# Cell2_Balancing.net
KiCad netlist of a schematic drawn in Altium Designer
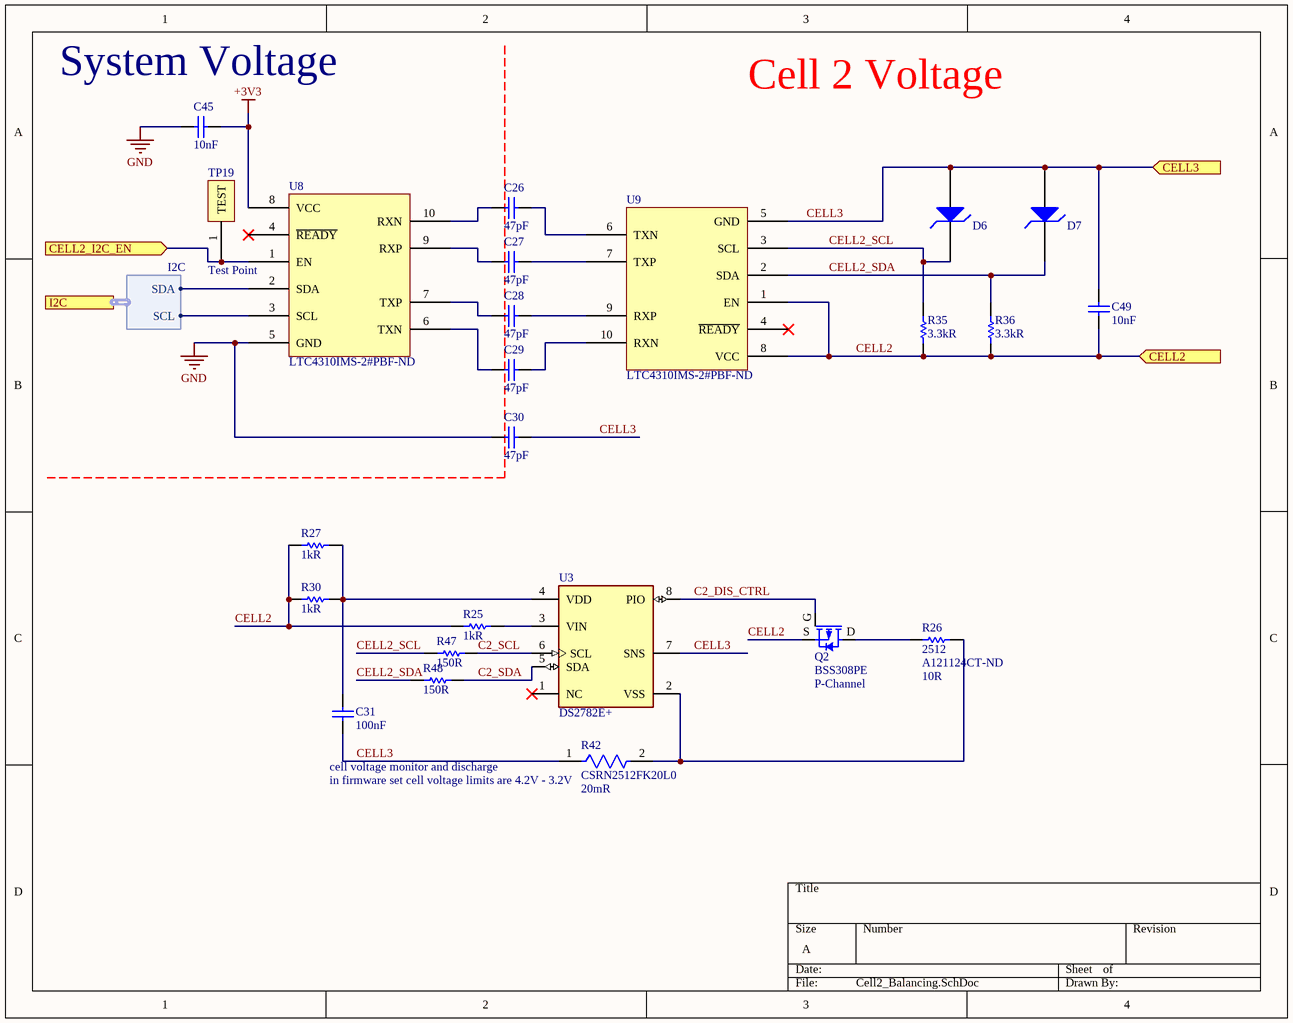
[diagram p0: Cell2_Balancing.SchDoc]

(export (version "E")
  (design (tool "Eeschema 10.0.6"))
  (components
    (comp (ref "C26")
      (value "06031A470FAT2A")
      (footprint "CAPC1608X90X35ML15T15")
      (fields (field (name "MANUFACTURER") "AVX Interconnect / Elco") (field (name "CAPACITANCE") "47pF"))
      (libsource (lib "Altium Content Vault") (part "CAP"))
    )
    (comp (ref "C27")
      (value "06031A470FAT2A")
      (footprint "CAPC1608X90X35ML15T15")
      (fields (field (name "MANUFACTURER") "AVX Interconnect / Elco") (field (name "CAPACITANCE") "47pF"))
      (libsource (lib "Altium Content Vault") (part "CAP"))
    )
    (comp (ref "C28")
      (value "06031A470FAT2A")
      (footprint "CAPC1608X90X35ML15T15")
      (fields (field (name "MANUFACTURER") "AVX Interconnect / Elco") (field (name "CAPACITANCE") "47pF"))
      (libsource (lib "Altium Content Vault") (part "CAP"))
    )
    (comp (ref "C29")
      (value "06031A470FAT2A")
      (footprint "CAPC1608X90X35ML15T15")
      (fields (field (name "MANUFACTURER") "AVX Interconnect / Elco") (field (name "CAPACITANCE") "47pF"))
      (libsource (lib "Altium Content Vault") (part "CAP"))
    )
    (comp (ref "C30")
      (value "06031A470FAT2A")
      (footprint "CAPC1608X90X35ML15T15")
      (fields (field (name "MANUFACTURER") "AVX Interconnect / Elco") (field (name "CAPACITANCE") "47pF"))
      (libsource (lib "Altium Content Vault") (part "CAP"))
    )
    (comp (ref "C31")
      (value "Capacitor 0402")
      (footprint "C0402")
      (description "CAP CER 0.1UF 25V X5R 0402 / High Value Multilayer Ceramic Capacitors (High dielectric type)")
      (fields
        (field (name "MANUFACTURER") "Taiyo Yuden")
        (field (name "MANUFACTURER PART NUMBER") "TMK105BJ104KV-F")
        (field (name "CAPACITANCE") "100nF")
      )
      (libsource (lib "Wally_BMS") (part "Capacitor 0402"))
    )
    (comp (ref "C45")
      (value "Capacitor 0402")
      (footprint "C0402")
      (description "Cap Ceramic 0.01uF 25V X7R 10% Pad SMD 0402 125C T/R")
      (fields
        (field (name "MANUFACTURER") "Samsung")
        (field (name "MANUFACTURER PART NUMBER") "CL05B103KA5NNNC")
        (field (name "CAPACITANCE") "10nF")
      )
      (libsource (lib "Wally_BMS") (part "Capacitor 0402"))
    )
    (comp (ref "C49")
      (value "Capacitor 0402")
      (footprint "C0402")
      (description "Cap Ceramic 0.01uF 25V X7R 10% Pad SMD 0402 125C T/R")
      (fields
        (field (name "MANUFACTURER") "Samsung")
        (field (name "MANUFACTURER PART NUMBER") "CL05B103KA5NNNC")
        (field (name "CAPACITANCE") "10nF")
      )
      (libsource (lib "Wally_BMS") (part "Capacitor 0402"))
    )
    (comp (ref "D6")
      (value "BZT52C4V7LP-7")
      (footprint "bzt52c4v7lp-7")
      (description "BZT52C4V7LP Series 4.7 V 10 mA Surface Mount Zener Diode - DFN1006-2")
      (fields (field (name "MANUFACTURER") "Diodes") (field (name "TOLERANCE") "6%"))
      (libsource (lib "Wally_BMS") (part "BZT52C4V7LP-7"))
    )
    (comp (ref "D7")
      (value "BZT52C4V7LP-7")
      (footprint "bzt52c4v7lp-7")
      (description "BZT52C4V7LP Series 4.7 V 10 mA Surface Mount Zener Diode - DFN1006-2")
      (fields (field (name "MANUFACTURER") "Diodes") (field (name "TOLERANCE") "6%"))
      (libsource (lib "Wally_BMS") (part "BZT52C4V7LP-7"))
    )
    (comp (ref "Q2")
      (value "BSS308PE")
      (footprint "BSS308PE")
      (description "MOSFET P-CH 30V 2A SOT23")
      (fields (field (name "FET TYPE") "P-Channel"))
      (libsource (lib "Transistors") (part "BSS308PE"))
    )
    (comp (ref "R25")
      (value "Resistor 0402")
      (footprint "RES0402")
      (description "Res Thick Film 0402 1K Ohm 1% 0.063W(1/16W) ±100ppm/C Pad SMD Automotive T/R")
      (fields
        (field (name "MANUFACTURER") "Stackpole Electronics")
        (field (name "MANUFACTURER PART NUMBER") "RMCF0402FT1K00")
        (field (name "RESISTANCE") "1kR")
      )
      (libsource (lib "Wally_BMS") (part "Resistor 0402"))
    )
    (comp (ref "R26")
      (value "Resistor 2512")
      (footprint "RES2512")
      (fields
        (field (name "PACKAGE / CASE") "2512")
        (field (name "SUPPLIER PART NUMBER 1") "A121124CT-ND")
        (field (name "MANUFACTURER") "TE Connectivity CGS")
        (field (name "MANUFACTURER PART NUMBER") "1-2176230-4")
        (field (name "RESISTANCE") "10R")
        (field (name "TOLERANCE") "5%")
      )
      (libsource (lib "Wally_BMS") (part "Resistor 2512"))
    )
    (comp (ref "R27")
      (value "Resistor 0402")
      (footprint "RES0402")
      (description "Res Thick Film 0402 1K Ohm 1% 0.063W(1/16W) ±100ppm/C Pad SMD Automotive T/R")
      (fields
        (field (name "MANUFACTURER") "Stackpole Electronics")
        (field (name "MANUFACTURER PART NUMBER") "RMCF0402FT1K00")
        (field (name "RESISTANCE") "1kR")
      )
      (libsource (lib "Wally_BMS") (part "Resistor 0402"))
    )
    (comp (ref "R30")
      (value "Resistor 0402")
      (footprint "RES0402")
      (description "Res Thick Film 0402 1K Ohm 1% 0.063W(1/16W) ±100ppm/C Pad SMD Automotive T/R")
      (fields
        (field (name "MANUFACTURER") "Stackpole Electronics")
        (field (name "MANUFACTURER PART NUMBER") "RMCF0402FT1K00")
        (field (name "RESISTANCE") "1kR")
      )
      (libsource (lib "Wally_BMS") (part "Resistor 0402"))
    )
    (comp (ref "R35")
      (value "Resistor 0402")
      (footprint "RES0402")
      (description "Res Thin Film 0402 3.3K Ohm 1% 1/16W ±50ppm/°C Molded SMD SMD Paper T/R")
      (fields
        (field (name "MANUFACTURER") "Yageo")
        (field (name "MANUFACTURER PART NUMBER") "RT0402FRE073K3L")
        (field (name "RESISTANCE") "3.3kR")
      )
      (libsource (lib "Wally_BMS") (part "Resistor 0402"))
    )
    (comp (ref "R36")
      (value "Resistor 0402")
      (footprint "RES0402")
      (description "Res Thin Film 0402 3.3K Ohm 1% 1/16W ±50ppm/°C Molded SMD SMD Paper T/R")
      (fields
        (field (name "MANUFACTURER") "Yageo")
        (field (name "MANUFACTURER PART NUMBER") "RT0402FRE073K3L")
        (field (name "RESISTANCE") "3.3kR")
      )
      (libsource (lib "Wally_BMS") (part "Resistor 0402"))
    )
    (comp (ref "R42")
      (value "CSRN2512FK20L0")
      (footprint "FP-CSRN2512-IPC_C")
      (description "Res Thick Film 2512 20mΩ 1% 2W ±200ppm/°C Molded SMD Plastic T/R")
      (fields (field (name "RESISTANCE") "20mR") (field (name "TOLERANCE") "1%"))
      (libsource (lib "Altium Content Vault") (part "1029c3af85768c4190bb7ad29bc67b5"))
    )
    (comp (ref "R47")
      (value "Resistor 0402")
      (footprint "RES0402")
      (description "Res Thin Film 0402 150 Ohm 1% 1/16W ±50ppm/°C Molded SMD SMD Paper T/R")
      (fields
        (field (name "MANUFACTURER") "Yageo")
        (field (name "MANUFACTURER PART NUMBER") "RT0402FRE07150RL")
        (field (name "RESISTANCE") "150R")
      )
      (libsource (lib "Wally_BMS") (part "Resistor 0402"))
    )
    (comp (ref "R48")
      (value "Resistor 0402")
      (footprint "RES0402")
      (description "Res Thin Film 0402 150 Ohm 1% 1/16W ±50ppm/°C Molded SMD SMD Paper T/R")
      (fields
        (field (name "MANUFACTURER") "Yageo")
        (field (name "MANUFACTURER PART NUMBER") "RT0402FRE07150RL")
        (field (name "RESISTANCE") "150R")
      )
      (libsource (lib "Wally_BMS") (part "Resistor 0402"))
    )
    (comp (ref "TP19")
      (value "Test Point")
      (footprint "TEST POINT")
      (libsource (lib "Wally_BMS") (part "Test Point"))
    )
    (comp (ref "U3")
      (value "DS2782E+")
      (footprint "FP-H8-2-MFG")
      (description "IC FUEL GAUGE BATT 8TSSOP")
      (fields
        (field (name "OCTOPART") "https://octopart.com/ds2782e%2B-maxim+integrated-8045252")
        (field (name "MANUFACTURER") "Maxim")
      )
      (libsource (lib "Altium Content Vault") (part "f9098ddd067e7739cd521d50be25c58"))
    )
    (comp (ref "U8")
      (value "LTC4310IMS-2#PBF-ND")
      (footprint "MSOP-10_MS_LIT")
      (description "DIGITAL ISOLATOR 2CH I2C 10MSOP")
      (libsource (lib "") (part "LTC4310IMS-2#PBF_1"))
    )
    (comp (ref "U9")
      (value "LTC4310IMS-2#PBF-ND")
      (footprint "MSOP-10_MS_LIT")
      (description "DIGITAL ISOLATOR 2CH I2C 10MSOP")
      (libsource (lib "Wally_BMS") (part "LTC4310IMS-2#PBF"))
    )
  )
  (nets
    (net (code "2") (name "+3V3") (class "Default")
      (node (ref "C45") (pin "1") (pinfunction "1_1") (pintype "passive"))
      (node (ref "U8") (pin "8") (pinfunction "VCC_8") (pintype "passive"))
    )
    (net (code "3") (name "/C2_DIS_CTRL") (class "Default")
      (node (ref "Q2") (pin "G") (pinfunction "G_G") (pintype "passive"))
      (node (ref "U3") (pin "8") (pinfunction "PIO_8") (pintype "bidirectional"))
    )
    (net (code "4") (name "/C2_SCL") (class "Default")
      (node (ref "R47") (pin "1") (pinfunction "1_1") (pintype "passive"))
      (node (ref "U3") (pin "6") (pinfunction "SCL_6") (pintype "input"))
    )
    (net (code "5") (name "/C2_SDA") (class "Default")
      (node (ref "R48") (pin "1") (pinfunction "1_1") (pintype "passive"))
      (node (ref "U3") (pin "5") (pinfunction "SDA_5") (pintype "bidirectional"))
    )
    (net (code "6") (name "/CELL2") (class "Default")
      (node (ref "C49") (pin "2") (pinfunction "2_2") (pintype "passive"))
      (node (ref "Q2") (pin "S") (pinfunction "3_S") (pintype "passive"))
      (node (ref "R25") (pin "1") (pinfunction "1_1") (pintype "passive"))
      (node (ref "R27") (pin "1") (pinfunction "1_1") (pintype "passive"))
      (node (ref "R30") (pin "1") (pinfunction "1_1") (pintype "passive"))
      (node (ref "R35") (pin "1") (pinfunction "1_1") (pintype "passive"))
      (node (ref "R36") (pin "1") (pinfunction "1_1") (pintype "passive"))
      (node (ref "U9") (pin "1") (pinfunction "EN_1") (pintype "passive"))
      (node (ref "U9") (pin "8") (pinfunction "VCC_8") (pintype "passive"))
    )
    (net (code "7") (name "/CELL2_I2C_EN") (class "Default")
      (node (ref "TP19") (pin "1") (pinfunction "TEST_1") (pintype "passive"))
      (node (ref "U8") (pin "1") (pinfunction "EN_1") (pintype "passive"))
    )
    (net (code "8") (name "/CELL2_SCL") (class "Default")
      (node (ref "D6") (pin "1") (pinfunction "K_1") (pintype "passive"))
      (node (ref "R35") (pin "2") (pinfunction "2_2") (pintype "passive"))
      (node (ref "R47") (pin "2") (pinfunction "2_2") (pintype "passive"))
      (node (ref "U9") (pin "3") (pinfunction "SCL_3") (pintype "passive"))
    )
    (net (code "9") (name "/CELL2_SDA") (class "Default")
      (node (ref "D7") (pin "1") (pinfunction "K_1") (pintype "passive"))
      (node (ref "R36") (pin "2") (pinfunction "2_2") (pintype "passive"))
      (node (ref "R48") (pin "2") (pinfunction "2_2") (pintype "passive"))
      (node (ref "U9") (pin "2") (pinfunction "SDA_2") (pintype "passive"))
    )
    (net (code "10") (name "/CELL3") (class "Default")
      (node (ref "C30") (pin "2") (pinfunction "2_2") (pintype "passive"))
      (node (ref "C31") (pin "1") (pinfunction "1_1") (pintype "passive"))
      (node (ref "C49") (pin "1") (pinfunction "1_1") (pintype "passive"))
      (node (ref "D6") (pin "2") (pinfunction "A_2") (pintype "passive"))
      (node (ref "D7") (pin "2") (pinfunction "A_2") (pintype "passive"))
      (node (ref "R42") (pin "1") (pinfunction "1_1") (pintype "passive"))
      (node (ref "U3") (pin "7") (pinfunction "SNS_7") (pintype "passive"))
      (node (ref "U9") (pin "5") (pinfunction "GND_5") (pintype "passive"))
    )
    (net (code "11") (name "/SCL") (class "Default")
      (node (ref "U8") (pin "3") (pinfunction "SCL_3") (pintype "passive"))
    )
    (net (code "12") (name "/SDA") (class "Default")
      (node (ref "U8") (pin "2") (pinfunction "SDA_2") (pintype "passive"))
    )
    (net (code "14") (name "GND") (class "Default")
      (node (ref "C30") (pin "1") (pinfunction "1_1") (pintype "passive"))
      (node (ref "C45") (pin "2") (pinfunction "2_2") (pintype "passive"))
      (node (ref "U8") (pin "5") (pinfunction "GND_5") (pintype "passive"))
    )
    (net (code "15") (name "Net-(Q2-PadD)") (class "Default")
      (node (ref "Q2") (pin "D") (pinfunction "D_D") (pintype "passive"))
      (node (ref "R26") (pin "1") (pinfunction "1_1") (pintype "passive"))
    )
    (net (code "16") (name "Net-(U3-VDD)") (class "Default")
      (node (ref "C31") (pin "2") (pinfunction "2_2") (pintype "passive"))
      (node (ref "R27") (pin "2") (pinfunction "2_2") (pintype "passive"))
      (node (ref "R30") (pin "2") (pinfunction "2_2") (pintype "passive"))
      (node (ref "U3") (pin "4") (pinfunction "VDD_4") (pintype "power_in"))
    )
    (net (code "17") (name "Net-(U3-VIN)") (class "Default")
      (node (ref "R25") (pin "2") (pinfunction "2_2") (pintype "passive"))
      (node (ref "U3") (pin "3") (pinfunction "VIN_3") (pintype "passive"))
    )
    (net (code "18") (name "Net-(U3-VSS)") (class "Default")
      (node (ref "R26") (pin "2") (pinfunction "2_2") (pintype "passive"))
      (node (ref "R42") (pin "2") (pinfunction "2_2") (pintype "passive"))
      (node (ref "U3") (pin "2") (pinfunction "VSS_2") (pintype "power_in"))
    )
    (net (code "19") (name "Net-(U8-RXN)") (class "Default")
      (node (ref "C26") (pin "1") (pinfunction "1_1") (pintype "passive"))
      (node (ref "U8") (pin "10") (pinfunction "RXN_10") (pintype "passive"))
    )
    (net (code "20") (name "Net-(U8-RXP)") (class "Default")
      (node (ref "C27") (pin "1") (pinfunction "1_1") (pintype "passive"))
      (node (ref "U8") (pin "9") (pinfunction "RXP_9") (pintype "passive"))
    )
    (net (code "21") (name "Net-(U8-TXN)") (class "Default")
      (node (ref "C29") (pin "1") (pinfunction "1_1") (pintype "passive"))
      (node (ref "U8") (pin "6") (pinfunction "TXN_6") (pintype "passive"))
    )
    (net (code "22") (name "Net-(U8-TXP)") (class "Default")
      (node (ref "C28") (pin "1") (pinfunction "1_1") (pintype "passive"))
      (node (ref "U8") (pin "7") (pinfunction "TXP_7") (pintype "passive"))
    )
    (net (code "23") (name "Net-(U9-RXN)") (class "Default")
      (node (ref "C29") (pin "2") (pinfunction "2_2") (pintype "passive"))
      (node (ref "U9") (pin "10") (pinfunction "RXN_10") (pintype "passive"))
    )
    (net (code "24") (name "Net-(U9-RXP)") (class "Default")
      (node (ref "C28") (pin "2") (pinfunction "2_2") (pintype "passive"))
      (node (ref "U9") (pin "9") (pinfunction "RXP_9") (pintype "passive"))
    )
    (net (code "25") (name "Net-(U9-TXN)") (class "Default")
      (node (ref "C26") (pin "2") (pinfunction "2_2") (pintype "passive"))
      (node (ref "U9") (pin "6") (pinfunction "TXN_6") (pintype "passive"))
    )
    (net (code "26") (name "Net-(U9-TXP)") (class "Default")
      (node (ref "C27") (pin "2") (pinfunction "2_2") (pintype "passive"))
      (node (ref "U9") (pin "7") (pinfunction "TXP_7") (pintype "passive"))
    )
    (net (code "27") (name "unconnected-(U3-NC-Pad1)") (class "Default")
      (node (ref "U3") (pin "1") (pinfunction "NC_1") (pintype "passive+no_connect"))
    )
    (net (code "28") (name "unconnected-(U8-~{READY}-Pad4)") (class "Default")
      (node (ref "U8") (pin "4") (pinfunction "~{READY}_4") (pintype "passive+no_connect"))
    )
    (net (code "29") (name "unconnected-(U9-~{READY}-Pad4)") (class "Default")
      (node (ref "U9") (pin "4") (pinfunction "~{READY}_4") (pintype "passive+no_connect"))
    )
  )
)
